# RcMPPT-Top.net
KiCad netlist of a schematic drawn in Altium Designer
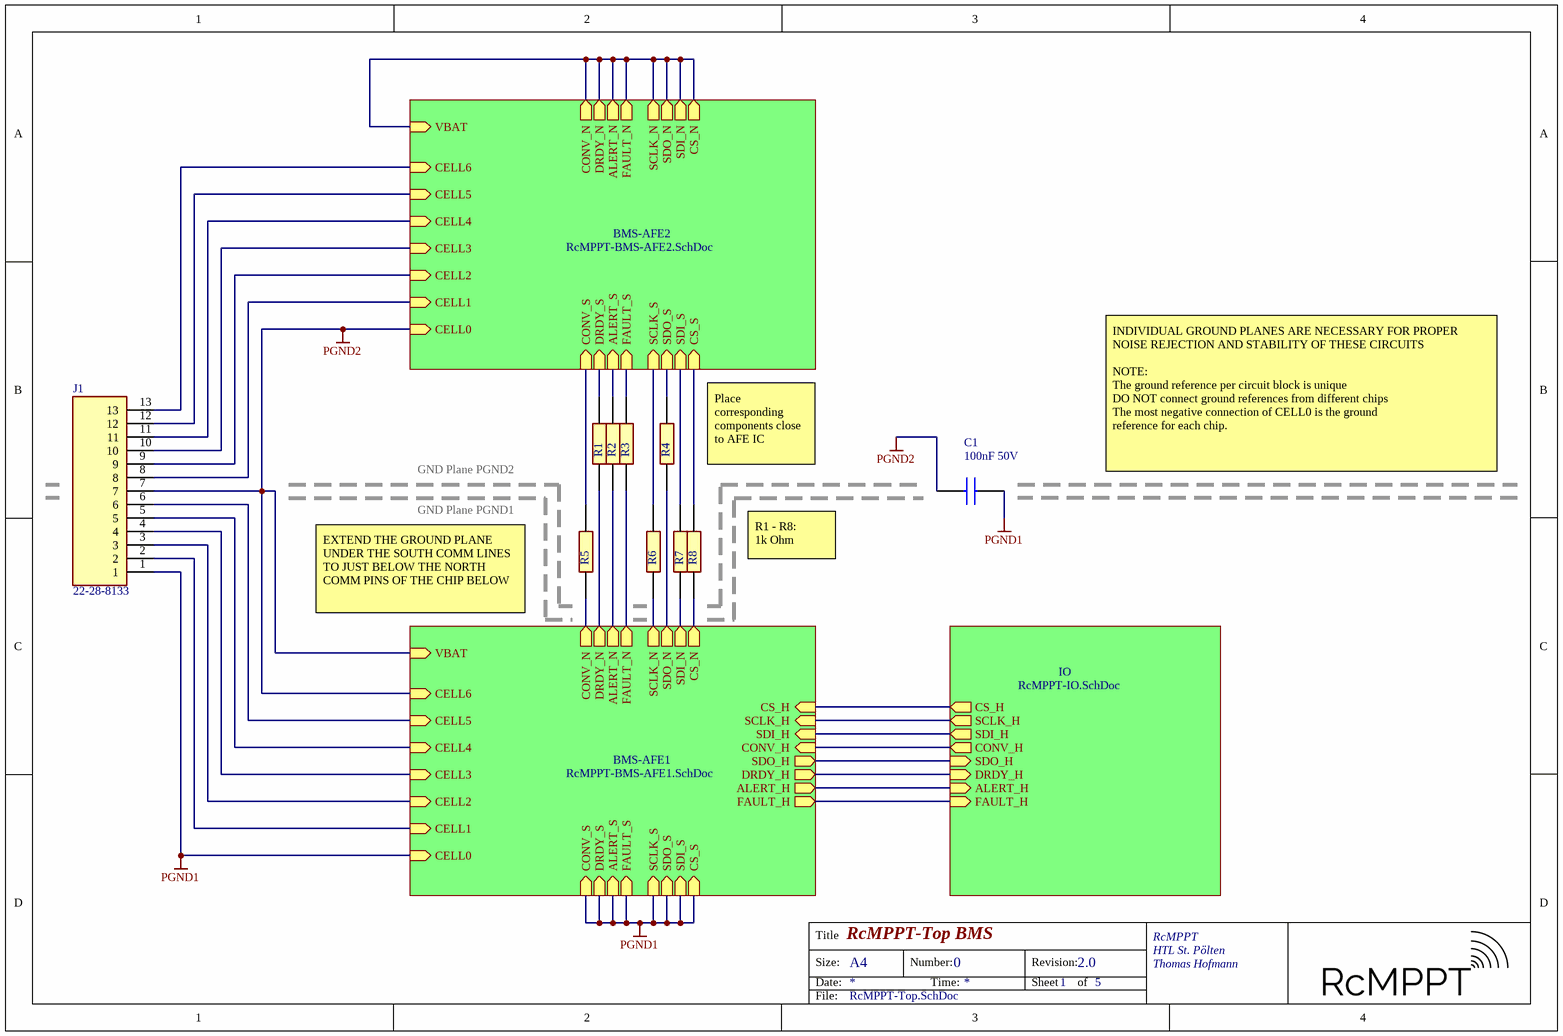
[diagram p0: RcMPPT-Top.SchDoc]

(export (version "E")
  (design (tool "Eeschema 10.0.6"))
  (components
    (comp (ref "C1")
      (value "100nF 50V")
      (footprint "CAPC1608X97N")
      (description "Capacitor")
      (libsource (lib "RcMPPTLib") (part "C0603"))
    )
    (comp (ref "J1")
      (value "22-28-8133")
      (footprint "HDRRA13W66P0X254_1X13_3302X229X249P")
      (description "Connector")
      (fields (field (name "MOUSER PART NUMBER") "538-22-28-8133"))
      (libsource (lib "RcMPPTLib") (part "22-28-8133"))
    )
    (comp (ref "R1")
      (value "1k")
      (footprint "RESC1005X40N")
      (description "Resistor")
      (libsource (lib "RcMPPTLib") (part "R0402"))
    )
    (comp (ref "R2")
      (value "1k")
      (footprint "RESC1005X40N")
      (description "Resistor")
      (libsource (lib "RcMPPTLib") (part "R0402"))
    )
    (comp (ref "R3")
      (value "1k")
      (footprint "RESC1005X40N")
      (description "Resistor")
      (libsource (lib "RcMPPTLib") (part "R0402"))
    )
    (comp (ref "R4")
      (value "1k")
      (footprint "RESC1005X40N")
      (description "Resistor")
      (libsource (lib "RcMPPTLib") (part "R0402"))
    )
    (comp (ref "R5")
      (value "1k")
      (footprint "RESC1005X40N")
      (description "Resistor")
      (libsource (lib "RcMPPTLib") (part "R0402"))
    )
    (comp (ref "R6")
      (value "1k")
      (footprint "RESC1005X40N")
      (description "Resistor")
      (libsource (lib "RcMPPTLib") (part "R0402"))
    )
    (comp (ref "R7")
      (value "1k")
      (footprint "RESC1005X40N")
      (description "Resistor")
      (libsource (lib "RcMPPTLib") (part "R0402"))
    )
    (comp (ref "R8")
      (value "1k")
      (footprint "RESC1005X40N")
      (description "Resistor")
      (libsource (lib "RcMPPTLib") (part "R0402"))
    )
  )
  (nets
    (net (code "3") (name "/ALERT_N_1") (class "Default")
      (node (ref "R2") (pin "1") (pinfunction "1_1") (pintype "passive"))
    )
    (net (code "4") (name "/ALERT_S") (class "Default")
      (node (ref "R2") (pin "2") (pinfunction "2_2") (pintype "passive"))
    )
    (net (code "5") (name "/CELL1") (class "Default")
      (node (ref "J1") (pin "8") (pinfunction "8_8") (pintype "passive"))
    )
    (net (code "6") (name "/CELL1_1") (class "Default")
      (node (ref "J1") (pin "2") (pinfunction "2_2") (pintype "passive"))
    )
    (net (code "7") (name "/CELL2") (class "Default")
      (node (ref "J1") (pin "9") (pinfunction "9_9") (pintype "passive"))
    )
    (net (code "8") (name "/CELL2_1") (class "Default")
      (node (ref "J1") (pin "3") (pinfunction "3_3") (pintype "passive"))
    )
    (net (code "9") (name "/CELL3") (class "Default")
      (node (ref "J1") (pin "10") (pinfunction "10_10") (pintype "passive"))
    )
    (net (code "10") (name "/CELL3_1") (class "Default")
      (node (ref "J1") (pin "4") (pinfunction "4_4") (pintype "passive"))
    )
    (net (code "11") (name "/CELL4") (class "Default")
      (node (ref "J1") (pin "11") (pinfunction "11_11") (pintype "passive"))
    )
    (net (code "12") (name "/CELL4_1") (class "Default")
      (node (ref "J1") (pin "5") (pinfunction "5_5") (pintype "passive"))
    )
    (net (code "13") (name "/CELL5") (class "Default")
      (node (ref "J1") (pin "12") (pinfunction "12_12") (pintype "passive"))
    )
    (net (code "14") (name "/CELL5_1") (class "Default")
      (node (ref "J1") (pin "6") (pinfunction "6_6") (pintype "passive"))
    )
    (net (code "15") (name "/CELL6") (class "Default")
      (node (ref "J1") (pin "13") (pinfunction "13_13") (pintype "passive"))
    )
    (net (code "17") (name "/CONV_N") (class "Default")
      (node (ref "R5") (pin "1") (pinfunction "1_1") (pintype "passive"))
    )
    (net (code "18") (name "/CONV_S") (class "Default")
      (node (ref "R5") (pin "2") (pinfunction "2_2") (pintype "passive"))
    )
    (net (code "20") (name "/CS_N") (class "Default")
      (node (ref "R8") (pin "1") (pinfunction "1_1") (pintype "passive"))
    )
    (net (code "21") (name "/CS_S") (class "Default")
      (node (ref "R8") (pin "2") (pinfunction "2_2") (pintype "passive"))
    )
    (net (code "23") (name "/DRDY_N") (class "Default")
      (node (ref "R1") (pin "1") (pinfunction "1_1") (pintype "passive"))
    )
    (net (code "24") (name "/DRDY_S") (class "Default")
      (node (ref "R1") (pin "2") (pinfunction "2_2") (pintype "passive"))
    )
    (net (code "26") (name "/FAULT_N") (class "Default")
      (node (ref "R3") (pin "1") (pinfunction "1_1") (pintype "passive"))
    )
    (net (code "27") (name "/FAULT_S") (class "Default")
      (node (ref "R3") (pin "2") (pinfunction "2_2") (pintype "passive"))
    )
    (net (code "29") (name "/SCLK_N") (class "Default")
      (node (ref "R6") (pin "1") (pinfunction "1_1") (pintype "passive"))
    )
    (net (code "30") (name "/SCLK_S") (class "Default")
      (node (ref "R6") (pin "2") (pinfunction "2_2") (pintype "passive"))
    )
    (net (code "32") (name "/SDI_N") (class "Default")
      (node (ref "R7") (pin "1") (pinfunction "1_1") (pintype "passive"))
    )
    (net (code "33") (name "/SDI_S") (class "Default")
      (node (ref "R7") (pin "2") (pinfunction "2_2") (pintype "passive"))
    )
    (net (code "35") (name "/SDO_N") (class "Default")
      (node (ref "R4") (pin "1") (pinfunction "1_1") (pintype "passive"))
    )
    (net (code "36") (name "/SDO_S") (class "Default")
      (node (ref "R4") (pin "2") (pinfunction "2_2") (pintype "passive"))
    )
    (net (code "37") (name "PGND1") (class "Default")
      (node (ref "C1") (pin "1") (pinfunction "1_1") (pintype "passive"))
      (node (ref "J1") (pin "1") (pinfunction "1_1") (pintype "passive"))
    )
    (net (code "38") (name "PGND2") (class "Default")
      (node (ref "C1") (pin "2") (pinfunction "2_2") (pintype "passive"))
      (node (ref "J1") (pin "7") (pinfunction "7_7") (pintype "passive"))
    )
  )
)
